# tubos.net
KiCad netlist of a schematic drawn in EAGLE
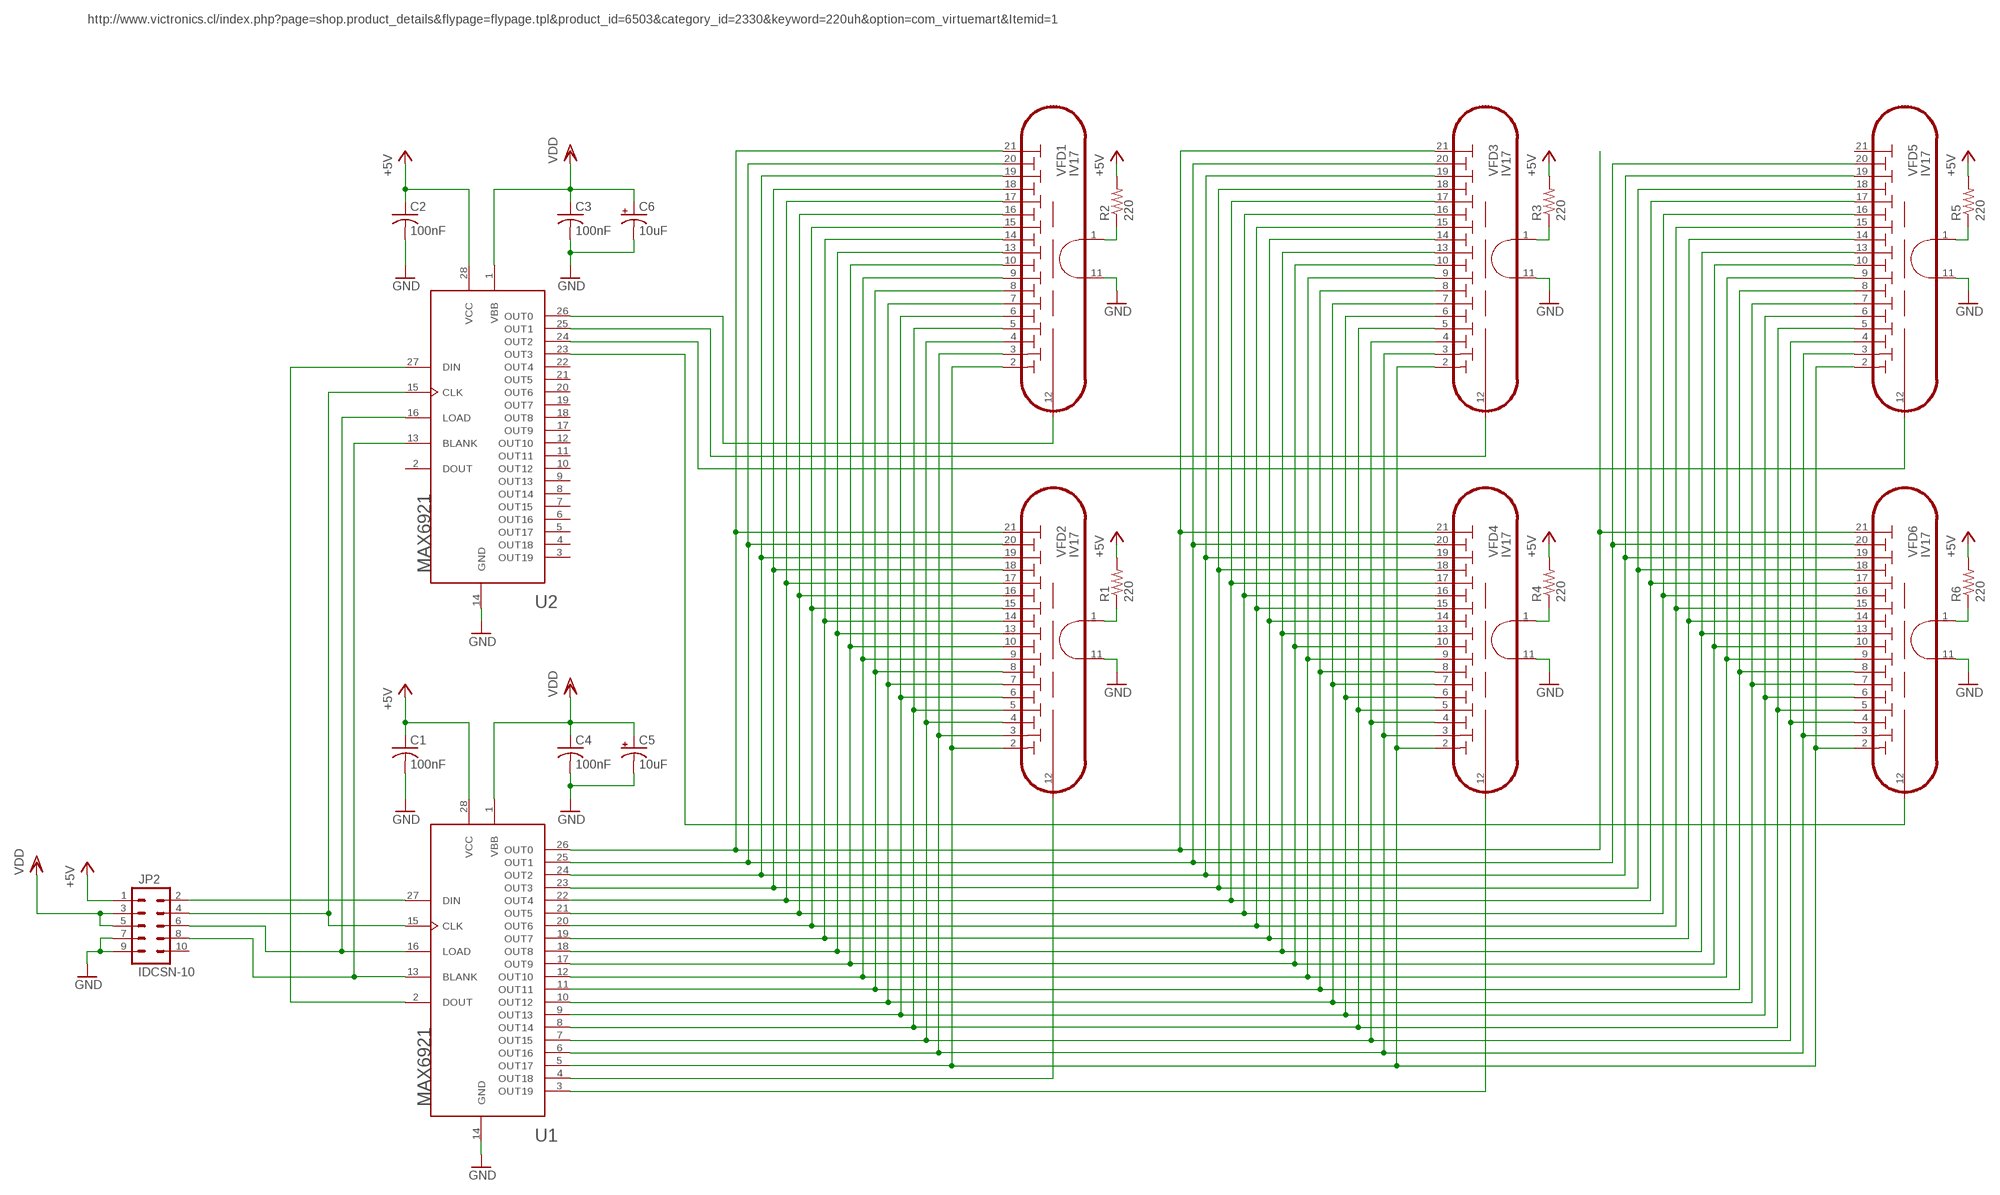
[diagram p0: schematic, sheet 1]

(export (version "E")
  (design (tool "Eeschema 10.0.6"))
  (components
    (comp (ref "C1")
      (value "100nF")
      (footprint "eagle-import:C1206")
      (libsource (lib "eagle-import") (part "C-USC1206"))
    )
    (comp (ref "C2")
      (value "100nF")
      (footprint "eagle-import:C1206")
      (libsource (lib "eagle-import") (part "C-USC1206"))
    )
    (comp (ref "C3")
      (value "100nF")
      (footprint "eagle-import:C1210")
      (libsource (lib "eagle-import") (part "C-USC1210"))
    )
    (comp (ref "C4")
      (value "100nF")
      (footprint "eagle-import:C1210")
      (libsource (lib "eagle-import") (part "C-USC1210"))
    )
    (comp (ref "C5")
      (value "NACEW100M100V6.3X8TR")
      (footprint "eagle-import:NACEW100M100V6.3X8TR")
      (libsource (lib "eagle-import") (part "NACEW100M100V6.3X8TR"))
    )
    (comp (ref "C6")
      (value "NACEW100M100V6.3X8TR")
      (footprint "eagle-import:NACEW100M100V6.3X8TR")
      (libsource (lib "eagle-import") (part "NACEW100M100V6.3X8TR"))
    )
    (comp (ref "JP2")
      (value "IDCSN-10")
      (footprint "eagle-import:IDCSN-10")
      (libsource (lib "eagle-import") (part "IDCSN-10"))
    )
    (comp (ref "R1")
      (value "220")
      (footprint "eagle-import:AXIAL-0.4")
      (libsource (lib "eagle-import") (part "RESISTORPTH-1/4W"))
    )
    (comp (ref "R2")
      (value "220")
      (footprint "eagle-import:AXIAL-0.4")
      (libsource (lib "eagle-import") (part "RESISTORPTH-1/4W"))
    )
    (comp (ref "R3")
      (value "220")
      (footprint "eagle-import:AXIAL-0.4")
      (libsource (lib "eagle-import") (part "RESISTORPTH-1/4W"))
    )
    (comp (ref "R4")
      (value "220")
      (footprint "eagle-import:AXIAL-0.4")
      (libsource (lib "eagle-import") (part "RESISTORPTH-1/4W"))
    )
    (comp (ref "R5")
      (value "220")
      (footprint "eagle-import:AXIAL-0.4")
      (libsource (lib "eagle-import") (part "RESISTORPTH-1/4W"))
    )
    (comp (ref "R6")
      (value "220")
      (footprint "eagle-import:AXIAL-0.4")
      (libsource (lib "eagle-import") (part "RESISTORPTH-1/4W"))
    )
    (comp (ref "U1")
      (value "MAX6921AWI")
      (footprint "eagle-import:SO28W")
      (libsource (lib "eagle-import") (part "MAX6921AWI"))
    )
    (comp (ref "U2")
      (value "MAX6921AWI")
      (footprint "eagle-import:SO28W")
      (libsource (lib "eagle-import") (part "MAX6921AWI"))
    )
    (comp (ref "VFD1")
      (value "IV17")
      (footprint "eagle-import:CIRCULAR")
      (libsource (lib "eagle-import") (part "IV17"))
    )
    (comp (ref "VFD2")
      (value "IV17")
      (footprint "eagle-import:CIRCULAR")
      (libsource (lib "eagle-import") (part "IV17"))
    )
    (comp (ref "VFD3")
      (value "IV17")
      (footprint "eagle-import:CIRCULAR")
      (libsource (lib "eagle-import") (part "IV17"))
    )
    (comp (ref "VFD4")
      (value "IV17")
      (footprint "eagle-import:CIRCULAR")
      (libsource (lib "eagle-import") (part "IV17"))
    )
    (comp (ref "VFD5")
      (value "IV17")
      (footprint "eagle-import:CIRCULAR")
      (libsource (lib "eagle-import") (part "IV17"))
    )
    (comp (ref "VFD6")
      (value "IV17")
      (footprint "eagle-import:CIRCULAR")
      (libsource (lib "eagle-import") (part "IV17"))
    )
  )
  (nets
    (net (code "1") (name "+5V") (class "Default")
      (node (ref "C1") (pin "1") (pinfunction "1_1") (pintype "passive"))
      (node (ref "C2") (pin "1") (pinfunction "1_1") (pintype "passive"))
      (node (ref "JP2") (pin "1") (pinfunction "1_1") (pintype "passive"))
      (node (ref "R1") (pin "P$2") (pinfunction "2_P$2") (pintype "passive"))
      (node (ref "R2") (pin "P$2") (pinfunction "2_P$2") (pintype "passive"))
      (node (ref "R3") (pin "P$2") (pinfunction "2_P$2") (pintype "passive"))
      (node (ref "R4") (pin "P$2") (pinfunction "2_P$2") (pintype "passive"))
      (node (ref "R5") (pin "P$2") (pinfunction "2_P$2") (pintype "passive"))
      (node (ref "R6") (pin "P$2") (pinfunction "2_P$2") (pintype "passive"))
      (node (ref "U1") (pin "28") (pinfunction "VCC_28") (pintype "power_in"))
      (node (ref "U2") (pin "28") (pinfunction "VCC_28") (pintype "power_in"))
    )
    (net (code "2") (name "GND") (class "Default")
      (node (ref "C1") (pin "2") (pinfunction "2_2") (pintype "passive"))
      (node (ref "C2") (pin "2") (pinfunction "2_2") (pintype "passive"))
      (node (ref "C3") (pin "2") (pinfunction "2_2") (pintype "passive"))
      (node (ref "C4") (pin "2") (pinfunction "2_2") (pintype "passive"))
      (node (ref "C5") (pin "NEG") (pinfunction "-_NEG") (pintype "passive"))
      (node (ref "C6") (pin "NEG") (pinfunction "-_NEG") (pintype "passive"))
      (node (ref "JP2") (pin "7") (pinfunction "7_7") (pintype "passive"))
      (node (ref "JP2") (pin "9") (pinfunction "9_9") (pintype "passive"))
      (node (ref "U1") (pin "14") (pinfunction "GND_14") (pintype "power_in"))
      (node (ref "U2") (pin "14") (pinfunction "GND_14") (pintype "power_in"))
      (node (ref "VFD1") (pin "11") (pinfunction "P$11_11") (pintype "bidirectional"))
      (node (ref "VFD2") (pin "11") (pinfunction "P$11_11") (pintype "bidirectional"))
      (node (ref "VFD3") (pin "11") (pinfunction "P$11_11") (pintype "bidirectional"))
      (node (ref "VFD4") (pin "11") (pinfunction "P$11_11") (pintype "bidirectional"))
      (node (ref "VFD5") (pin "11") (pinfunction "P$11_11") (pintype "bidirectional"))
      (node (ref "VFD6") (pin "11") (pinfunction "P$11_11") (pintype "bidirectional"))
    )
    (net (code "3") (name "Net-(R1-1)") (class "Default")
      (node (ref "R1") (pin "P$1") (pinfunction "1_P$1") (pintype "passive"))
      (node (ref "VFD2") (pin "1") (pinfunction "P$1_1") (pintype "bidirectional"))
    )
    (net (code "4") (name "Net-(R2-1)") (class "Default")
      (node (ref "R2") (pin "P$1") (pinfunction "1_P$1") (pintype "passive"))
      (node (ref "VFD1") (pin "1") (pinfunction "P$1_1") (pintype "bidirectional"))
    )
    (net (code "5") (name "Net-(R3-1)") (class "Default")
      (node (ref "R3") (pin "P$1") (pinfunction "1_P$1") (pintype "passive"))
      (node (ref "VFD3") (pin "1") (pinfunction "P$1_1") (pintype "bidirectional"))
    )
    (net (code "6") (name "Net-(R4-1)") (class "Default")
      (node (ref "R4") (pin "P$1") (pinfunction "1_P$1") (pintype "passive"))
      (node (ref "VFD4") (pin "1") (pinfunction "P$1_1") (pintype "bidirectional"))
    )
    (net (code "7") (name "Net-(R5-1)") (class "Default")
      (node (ref "R5") (pin "P$1") (pinfunction "1_P$1") (pintype "passive"))
      (node (ref "VFD5") (pin "1") (pinfunction "P$1_1") (pintype "bidirectional"))
    )
    (net (code "8") (name "Net-(R6-1)") (class "Default")
      (node (ref "R6") (pin "P$1") (pinfunction "1_P$1") (pintype "passive"))
      (node (ref "VFD6") (pin "1") (pinfunction "P$1_1") (pintype "bidirectional"))
    )
    (net (code "9") (name "Net-(U1-BLANK)") (class "Default")
      (node (ref "JP2") (pin "8") (pinfunction "8_8") (pintype "passive"))
      (node (ref "U1") (pin "13") (pinfunction "BLANK_13") (pintype "input"))
      (node (ref "U2") (pin "13") (pinfunction "BLANK_13") (pintype "input"))
    )
    (net (code "10") (name "Net-(U1-CLK)") (class "Default")
      (node (ref "JP2") (pin "4") (pinfunction "4_4") (pintype "passive"))
      (node (ref "U1") (pin "15") (pinfunction "CLK_15") (pintype "input"))
      (node (ref "U2") (pin "15") (pinfunction "CLK_15") (pintype "input"))
    )
    (net (code "11") (name "Net-(U1-DIN)") (class "Default")
      (node (ref "JP2") (pin "2") (pinfunction "2_2") (pintype "passive"))
      (node (ref "U1") (pin "27") (pinfunction "DIN_27") (pintype "input"))
    )
    (net (code "12") (name "Net-(U1-DOUT)") (class "Default")
      (node (ref "U1") (pin "2") (pinfunction "DOUT_2") (pintype "output"))
      (node (ref "U2") (pin "27") (pinfunction "DIN_27") (pintype "input"))
    )
    (net (code "13") (name "Net-(U1-LOAD)") (class "Default")
      (node (ref "JP2") (pin "6") (pinfunction "6_6") (pintype "passive"))
      (node (ref "U1") (pin "16") (pinfunction "LOAD_16") (pintype "input"))
      (node (ref "U2") (pin "16") (pinfunction "LOAD_16") (pintype "input"))
    )
    (net (code "14") (name "Net-(U1-OUT0)") (class "Default")
      (node (ref "U1") (pin "26") (pinfunction "OUT0_26") (pintype "output"))
      (node (ref "VFD1") (pin "21") (pinfunction "P$21_21") (pintype "input"))
      (node (ref "VFD2") (pin "21") (pinfunction "P$21_21") (pintype "input"))
      (node (ref "VFD3") (pin "21") (pinfunction "P$21_21") (pintype "input"))
      (node (ref "VFD4") (pin "21") (pinfunction "P$21_21") (pintype "input"))
      (node (ref "VFD6") (pin "21") (pinfunction "P$21_21") (pintype "input"))
    )
    (net (code "15") (name "Net-(U1-OUT1)") (class "Default")
      (node (ref "U1") (pin "25") (pinfunction "OUT1_25") (pintype "output"))
      (node (ref "VFD1") (pin "20") (pinfunction "P$20_20") (pintype "input"))
      (node (ref "VFD2") (pin "20") (pinfunction "P$20_20") (pintype "input"))
      (node (ref "VFD3") (pin "20") (pinfunction "P$20_20") (pintype "input"))
      (node (ref "VFD4") (pin "20") (pinfunction "P$20_20") (pintype "input"))
      (node (ref "VFD5") (pin "20") (pinfunction "P$20_20") (pintype "input"))
      (node (ref "VFD6") (pin "20") (pinfunction "P$20_20") (pintype "input"))
    )
    (net (code "16") (name "Net-(U1-OUT2)") (class "Default")
      (node (ref "U1") (pin "24") (pinfunction "OUT2_24") (pintype "output"))
      (node (ref "VFD1") (pin "19") (pinfunction "P$19_19") (pintype "input"))
      (node (ref "VFD2") (pin "19") (pinfunction "P$19_19") (pintype "input"))
      (node (ref "VFD3") (pin "19") (pinfunction "P$19_19") (pintype "input"))
      (node (ref "VFD4") (pin "19") (pinfunction "P$19_19") (pintype "input"))
      (node (ref "VFD5") (pin "19") (pinfunction "P$19_19") (pintype "input"))
      (node (ref "VFD6") (pin "19") (pinfunction "P$19_19") (pintype "input"))
    )
    (net (code "17") (name "Net-(U1-OUT3)") (class "Default")
      (node (ref "U1") (pin "23") (pinfunction "OUT3_23") (pintype "output"))
      (node (ref "VFD1") (pin "18") (pinfunction "P$18_18") (pintype "input"))
      (node (ref "VFD2") (pin "18") (pinfunction "P$18_18") (pintype "input"))
      (node (ref "VFD3") (pin "18") (pinfunction "P$18_18") (pintype "input"))
      (node (ref "VFD4") (pin "18") (pinfunction "P$18_18") (pintype "input"))
      (node (ref "VFD5") (pin "18") (pinfunction "P$18_18") (pintype "input"))
      (node (ref "VFD6") (pin "18") (pinfunction "P$18_18") (pintype "input"))
    )
    (net (code "18") (name "Net-(U1-OUT4)") (class "Default")
      (node (ref "U1") (pin "22") (pinfunction "OUT4_22") (pintype "output"))
      (node (ref "VFD1") (pin "17") (pinfunction "P$17_17") (pintype "input"))
      (node (ref "VFD2") (pin "17") (pinfunction "P$17_17") (pintype "input"))
      (node (ref "VFD3") (pin "17") (pinfunction "P$17_17") (pintype "input"))
      (node (ref "VFD4") (pin "17") (pinfunction "P$17_17") (pintype "input"))
      (node (ref "VFD5") (pin "17") (pinfunction "P$17_17") (pintype "input"))
      (node (ref "VFD6") (pin "17") (pinfunction "P$17_17") (pintype "input"))
    )
    (net (code "19") (name "Net-(U1-OUT5)") (class "Default")
      (node (ref "U1") (pin "21") (pinfunction "OUT5_21") (pintype "output"))
      (node (ref "VFD1") (pin "16") (pinfunction "P$16_16") (pintype "input"))
      (node (ref "VFD2") (pin "16") (pinfunction "P$16_16") (pintype "input"))
      (node (ref "VFD3") (pin "16") (pinfunction "P$16_16") (pintype "input"))
      (node (ref "VFD4") (pin "16") (pinfunction "P$16_16") (pintype "input"))
      (node (ref "VFD5") (pin "16") (pinfunction "P$16_16") (pintype "input"))
      (node (ref "VFD6") (pin "16") (pinfunction "P$16_16") (pintype "input"))
    )
    (net (code "20") (name "Net-(U1-OUT6)") (class "Default")
      (node (ref "U1") (pin "20") (pinfunction "OUT6_20") (pintype "output"))
      (node (ref "VFD1") (pin "15") (pinfunction "P$15_15") (pintype "input"))
      (node (ref "VFD2") (pin "15") (pinfunction "P$15_15") (pintype "input"))
      (node (ref "VFD3") (pin "15") (pinfunction "P$15_15") (pintype "input"))
      (node (ref "VFD4") (pin "15") (pinfunction "P$15_15") (pintype "input"))
      (node (ref "VFD5") (pin "15") (pinfunction "P$15_15") (pintype "input"))
      (node (ref "VFD6") (pin "15") (pinfunction "P$15_15") (pintype "input"))
    )
    (net (code "21") (name "Net-(U1-OUT7)") (class "Default")
      (node (ref "U1") (pin "19") (pinfunction "OUT7_19") (pintype "output"))
      (node (ref "VFD1") (pin "14") (pinfunction "P$14_14") (pintype "input"))
      (node (ref "VFD2") (pin "14") (pinfunction "P$14_14") (pintype "input"))
      (node (ref "VFD3") (pin "14") (pinfunction "P$14_14") (pintype "input"))
      (node (ref "VFD4") (pin "14") (pinfunction "P$14_14") (pintype "input"))
      (node (ref "VFD5") (pin "14") (pinfunction "P$14_14") (pintype "input"))
      (node (ref "VFD6") (pin "14") (pinfunction "P$14_14") (pintype "input"))
    )
    (net (code "22") (name "Net-(U1-OUT8)") (class "Default")
      (node (ref "U1") (pin "18") (pinfunction "OUT8_18") (pintype "output"))
      (node (ref "VFD1") (pin "13") (pinfunction "P$13_13") (pintype "input"))
      (node (ref "VFD2") (pin "13") (pinfunction "P$13_13") (pintype "input"))
      (node (ref "VFD3") (pin "13") (pinfunction "P$13_13") (pintype "input"))
      (node (ref "VFD4") (pin "13") (pinfunction "P$13_13") (pintype "input"))
      (node (ref "VFD5") (pin "13") (pinfunction "P$13_13") (pintype "input"))
      (node (ref "VFD6") (pin "13") (pinfunction "P$13_13") (pintype "input"))
    )
    (net (code "23") (name "Net-(U1-OUT9)") (class "Default")
      (node (ref "U1") (pin "17") (pinfunction "OUT9_17") (pintype "output"))
      (node (ref "VFD1") (pin "10") (pinfunction "P$10_10") (pintype "input"))
      (node (ref "VFD2") (pin "10") (pinfunction "P$10_10") (pintype "input"))
      (node (ref "VFD3") (pin "10") (pinfunction "P$10_10") (pintype "input"))
      (node (ref "VFD4") (pin "10") (pinfunction "P$10_10") (pintype "input"))
      (node (ref "VFD5") (pin "10") (pinfunction "P$10_10") (pintype "input"))
      (node (ref "VFD6") (pin "10") (pinfunction "P$10_10") (pintype "input"))
    )
    (net (code "24") (name "Net-(U1-OUT10)") (class "Default")
      (node (ref "U1") (pin "12") (pinfunction "OUT10_12") (pintype "output"))
      (node (ref "VFD1") (pin "9") (pinfunction "P$9_9") (pintype "input"))
      (node (ref "VFD2") (pin "9") (pinfunction "P$9_9") (pintype "input"))
      (node (ref "VFD3") (pin "9") (pinfunction "P$9_9") (pintype "input"))
      (node (ref "VFD4") (pin "9") (pinfunction "P$9_9") (pintype "input"))
      (node (ref "VFD5") (pin "9") (pinfunction "P$9_9") (pintype "input"))
      (node (ref "VFD6") (pin "9") (pinfunction "P$9_9") (pintype "input"))
    )
    (net (code "25") (name "Net-(U1-OUT11)") (class "Default")
      (node (ref "U1") (pin "11") (pinfunction "OUT11_11") (pintype "output"))
      (node (ref "VFD1") (pin "8") (pinfunction "P$8_8") (pintype "input"))
      (node (ref "VFD2") (pin "8") (pinfunction "P$8_8") (pintype "input"))
      (node (ref "VFD3") (pin "8") (pinfunction "P$8_8") (pintype "input"))
      (node (ref "VFD4") (pin "8") (pinfunction "P$8_8") (pintype "input"))
      (node (ref "VFD5") (pin "8") (pinfunction "P$8_8") (pintype "input"))
      (node (ref "VFD6") (pin "8") (pinfunction "P$8_8") (pintype "input"))
    )
    (net (code "26") (name "Net-(U1-OUT12)") (class "Default")
      (node (ref "U1") (pin "10") (pinfunction "OUT12_10") (pintype "output"))
      (node (ref "VFD1") (pin "7") (pinfunction "P$7_7") (pintype "input"))
      (node (ref "VFD2") (pin "7") (pinfunction "P$7_7") (pintype "input"))
      (node (ref "VFD3") (pin "7") (pinfunction "P$7_7") (pintype "input"))
      (node (ref "VFD4") (pin "7") (pinfunction "P$7_7") (pintype "input"))
      (node (ref "VFD5") (pin "7") (pinfunction "P$7_7") (pintype "input"))
      (node (ref "VFD6") (pin "7") (pinfunction "P$7_7") (pintype "input"))
    )
    (net (code "27") (name "Net-(U1-OUT13)") (class "Default")
      (node (ref "U1") (pin "9") (pinfunction "OUT13_9") (pintype "output"))
      (node (ref "VFD1") (pin "6") (pinfunction "P$6_6") (pintype "input"))
      (node (ref "VFD2") (pin "6") (pinfunction "P$6_6") (pintype "input"))
      (node (ref "VFD3") (pin "6") (pinfunction "P$6_6") (pintype "input"))
      (node (ref "VFD4") (pin "6") (pinfunction "P$6_6") (pintype "input"))
      (node (ref "VFD5") (pin "6") (pinfunction "P$6_6") (pintype "input"))
      (node (ref "VFD6") (pin "6") (pinfunction "P$6_6") (pintype "input"))
    )
    (net (code "28") (name "Net-(U1-OUT14)") (class "Default")
      (node (ref "U1") (pin "8") (pinfunction "OUT14_8") (pintype "output"))
      (node (ref "VFD1") (pin "5") (pinfunction "P$5_5") (pintype "input"))
      (node (ref "VFD2") (pin "5") (pinfunction "P$5_5") (pintype "input"))
      (node (ref "VFD3") (pin "5") (pinfunction "P$5_5") (pintype "input"))
      (node (ref "VFD4") (pin "5") (pinfunction "P$5_5") (pintype "input"))
      (node (ref "VFD5") (pin "5") (pinfunction "P$5_5") (pintype "input"))
      (node (ref "VFD6") (pin "5") (pinfunction "P$5_5") (pintype "input"))
    )
    (net (code "29") (name "Net-(U1-OUT15)") (class "Default")
      (node (ref "U1") (pin "7") (pinfunction "OUT15_7") (pintype "output"))
      (node (ref "VFD1") (pin "4") (pinfunction "P$4_4") (pintype "input"))
      (node (ref "VFD2") (pin "4") (pinfunction "P$4_4") (pintype "input"))
      (node (ref "VFD3") (pin "4") (pinfunction "P$4_4") (pintype "input"))
      (node (ref "VFD4") (pin "4") (pinfunction "P$4_4") (pintype "input"))
      (node (ref "VFD5") (pin "4") (pinfunction "P$4_4") (pintype "input"))
      (node (ref "VFD6") (pin "4") (pinfunction "P$4_4") (pintype "input"))
    )
    (net (code "30") (name "Net-(U1-OUT16)") (class "Default")
      (node (ref "U1") (pin "6") (pinfunction "OUT16_6") (pintype "output"))
      (node (ref "VFD1") (pin "3") (pinfunction "P$3_3") (pintype "input"))
      (node (ref "VFD2") (pin "3") (pinfunction "P$3_3") (pintype "input"))
      (node (ref "VFD3") (pin "3") (pinfunction "P$3_3") (pintype "input"))
      (node (ref "VFD4") (pin "3") (pinfunction "P$3_3") (pintype "input"))
      (node (ref "VFD5") (pin "3") (pinfunction "P$3_3") (pintype "input"))
      (node (ref "VFD6") (pin "3") (pinfunction "P$3_3") (pintype "input"))
    )
    (net (code "31") (name "Net-(U1-OUT17)") (class "Default")
      (node (ref "U1") (pin "5") (pinfunction "OUT17_5") (pintype "output"))
      (node (ref "VFD1") (pin "2") (pinfunction "P$2_2") (pintype "input"))
      (node (ref "VFD2") (pin "2") (pinfunction "P$2_2") (pintype "input"))
      (node (ref "VFD3") (pin "2") (pinfunction "P$2_2") (pintype "input"))
      (node (ref "VFD4") (pin "2") (pinfunction "P$2_2") (pintype "input"))
      (node (ref "VFD5") (pin "2") (pinfunction "P$2_2") (pintype "input"))
      (node (ref "VFD6") (pin "2") (pinfunction "P$2_2") (pintype "input"))
    )
    (net (code "32") (name "Net-(U1-OUT18)") (class "Default")
      (node (ref "U1") (pin "4") (pinfunction "OUT18_4") (pintype "output"))
      (node (ref "VFD2") (pin "12") (pinfunction "P$12_12") (pintype "input"))
    )
    (net (code "33") (name "Net-(U1-OUT19)") (class "Default")
      (node (ref "U1") (pin "3") (pinfunction "OUT19_3") (pintype "output"))
      (node (ref "VFD4") (pin "12") (pinfunction "P$12_12") (pintype "input"))
    )
    (net (code "34") (name "Net-(U2-OUT0)") (class "Default")
      (node (ref "U2") (pin "26") (pinfunction "OUT0_26") (pintype "output"))
      (node (ref "VFD1") (pin "12") (pinfunction "P$12_12") (pintype "input"))
    )
    (net (code "35") (name "Net-(U2-OUT1)") (class "Default")
      (node (ref "U2") (pin "25") (pinfunction "OUT1_25") (pintype "output"))
      (node (ref "VFD3") (pin "12") (pinfunction "P$12_12") (pintype "input"))
    )
    (net (code "36") (name "Net-(U2-OUT2)") (class "Default")
      (node (ref "U2") (pin "24") (pinfunction "OUT2_24") (pintype "output"))
      (node (ref "VFD5") (pin "12") (pinfunction "P$12_12") (pintype "input"))
    )
    (net (code "37") (name "Net-(U2-OUT3)") (class "Default")
      (node (ref "U2") (pin "23") (pinfunction "OUT3_23") (pintype "output"))
      (node (ref "VFD6") (pin "12") (pinfunction "P$12_12") (pintype "input"))
    )
    (net (code "38") (name "VDD") (class "Default")
      (node (ref "C3") (pin "1") (pinfunction "1_1") (pintype "passive"))
      (node (ref "C4") (pin "1") (pinfunction "1_1") (pintype "passive"))
      (node (ref "C5") (pin "POS") (pinfunction "+_POS") (pintype "passive"))
      (node (ref "C6") (pin "POS") (pinfunction "+_POS") (pintype "passive"))
      (node (ref "JP2") (pin "3") (pinfunction "3_3") (pintype "passive"))
      (node (ref "JP2") (pin "5") (pinfunction "5_5") (pintype "passive"))
      (node (ref "U1") (pin "1") (pinfunction "VBB_1") (pintype "power_in"))
      (node (ref "U2") (pin "1") (pinfunction "VBB_1") (pintype "power_in"))
    )
    (net (code "39") (name "unconnected-(JP2-Pad10)") (class "Default")
      (node (ref "JP2") (pin "10") (pinfunction "10_10") (pintype "passive"))
    )
    (net (code "40") (name "unconnected-(U2-DOUT-Pad2)") (class "Default")
      (node (ref "U2") (pin "2") (pinfunction "DOUT_2") (pintype "output"))
    )
    (net (code "41") (name "unconnected-(U2-OUT4-Pad22)") (class "Default")
      (node (ref "U2") (pin "22") (pinfunction "OUT4_22") (pintype "output"))
    )
    (net (code "42") (name "unconnected-(U2-OUT5-Pad21)") (class "Default")
      (node (ref "U2") (pin "21") (pinfunction "OUT5_21") (pintype "output"))
    )
    (net (code "43") (name "unconnected-(U2-OUT6-Pad20)") (class "Default")
      (node (ref "U2") (pin "20") (pinfunction "OUT6_20") (pintype "output"))
    )
    (net (code "44") (name "unconnected-(U2-OUT7-Pad19)") (class "Default")
      (node (ref "U2") (pin "19") (pinfunction "OUT7_19") (pintype "output"))
    )
    (net (code "45") (name "unconnected-(U2-OUT8-Pad18)") (class "Default")
      (node (ref "U2") (pin "18") (pinfunction "OUT8_18") (pintype "output"))
    )
    (net (code "46") (name "unconnected-(U2-OUT9-Pad17)") (class "Default")
      (node (ref "U2") (pin "17") (pinfunction "OUT9_17") (pintype "output"))
    )
    (net (code "47") (name "unconnected-(U2-OUT10-Pad12)") (class "Default")
      (node (ref "U2") (pin "12") (pinfunction "OUT10_12") (pintype "output"))
    )
    (net (code "48") (name "unconnected-(U2-OUT11-Pad11)") (class "Default")
      (node (ref "U2") (pin "11") (pinfunction "OUT11_11") (pintype "output"))
    )
    (net (code "49") (name "unconnected-(U2-OUT12-Pad10)") (class "Default")
      (node (ref "U2") (pin "10") (pinfunction "OUT12_10") (pintype "output"))
    )
    (net (code "50") (name "unconnected-(U2-OUT13-Pad9)") (class "Default")
      (node (ref "U2") (pin "9") (pinfunction "OUT13_9") (pintype "output"))
    )
    (net (code "51") (name "unconnected-(U2-OUT14-Pad8)") (class "Default")
      (node (ref "U2") (pin "8") (pinfunction "OUT14_8") (pintype "output"))
    )
    (net (code "52") (name "unconnected-(U2-OUT15-Pad7)") (class "Default")
      (node (ref "U2") (pin "7") (pinfunction "OUT15_7") (pintype "output"))
    )
    (net (code "53") (name "unconnected-(U2-OUT16-Pad6)") (class "Default")
      (node (ref "U2") (pin "6") (pinfunction "OUT16_6") (pintype "output"))
    )
    (net (code "54") (name "unconnected-(U2-OUT17-Pad5)") (class "Default")
      (node (ref "U2") (pin "5") (pinfunction "OUT17_5") (pintype "output"))
    )
    (net (code "55") (name "unconnected-(U2-OUT18-Pad4)") (class "Default")
      (node (ref "U2") (pin "4") (pinfunction "OUT18_4") (pintype "output"))
    )
    (net (code "56") (name "unconnected-(U2-OUT19-Pad3)") (class "Default")
      (node (ref "U2") (pin "3") (pinfunction "OUT19_3") (pintype "output"))
    )
    (net (code "57") (name "unconnected-(VFD5-P$21-Pad21)") (class "Default")
      (node (ref "VFD5") (pin "21") (pinfunction "P$21_21") (pintype "input"))
    )
  )
)
